# ToolPCB.net
KiCad netlist of a schematic drawn in EAGLE
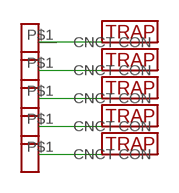
[diagram p0: schematic, sheet 1]

(export (version "E")
  (design (tool "Eeschema 10.0.6"))
  (components
    (comp (ref "U$1")
      (value "MOLEX-LITE-TRAP")
      (footprint "eagle-import:MOLEX-LITE-TRAP")
      (libsource (lib "eagle-import") (part "MOLEX-LITE-TRAP"))
    )
    (comp (ref "U$2")
      (value "MOLEX-LITE-TRAP")
      (footprint "eagle-import:MOLEX-LITE-TRAP")
      (libsource (lib "eagle-import") (part "MOLEX-LITE-TRAP"))
    )
    (comp (ref "U$3")
      (value "MOLEX-LITE-TRAP")
      (footprint "eagle-import:MOLEX-LITE-TRAP")
      (libsource (lib "eagle-import") (part "MOLEX-LITE-TRAP"))
    )
    (comp (ref "U$4")
      (value "MOLEX-LITE-TRAP")
      (footprint "eagle-import:MOLEX-LITE-TRAP")
      (libsource (lib "eagle-import") (part "MOLEX-LITE-TRAP"))
    )
    (comp (ref "U$5")
      (value "MOLEX-LITE-TRAP")
      (footprint "eagle-import:MOLEX-LITE-TRAP")
      (libsource (lib "eagle-import") (part "MOLEX-LITE-TRAP"))
    )
    (comp (ref "U$6")
      (value "B_CONTACT")
      (footprint "eagle-import:B_CONTACT")
      (libsource (lib "eagle-import") (part "B_CONTACT"))
    )
    (comp (ref "U$7")
      (value "B_CONTACT")
      (footprint "eagle-import:B_CONTACT")
      (libsource (lib "eagle-import") (part "B_CONTACT"))
    )
    (comp (ref "U$8")
      (value "B_CONTACT")
      (footprint "eagle-import:B_CONTACT")
      (libsource (lib "eagle-import") (part "B_CONTACT"))
    )
    (comp (ref "U$9")
      (value "B_CONTACT")
      (footprint "eagle-import:B_CONTACT")
      (libsource (lib "eagle-import") (part "B_CONTACT"))
    )
    (comp (ref "U$10")
      (value "B_CONTACT")
      (footprint "eagle-import:B_CONTACT")
      (libsource (lib "eagle-import") (part "B_CONTACT"))
    )
  )
  (nets
    (net (code "1") (name "Net-(U$1-CON)") (class "Default")
      (node (ref "U$1") (pin "TRAP") (pinfunction "CON_TRAP") (pintype "bidirectional"))
      (node (ref "U$8") (pin "P$1") (pinfunction "CNCT_P$1") (pintype "bidirectional"))
    )
    (net (code "2") (name "Net-(U$2-CON)") (class "Default")
      (node (ref "U$2") (pin "TRAP") (pinfunction "CON_TRAP") (pintype "bidirectional"))
      (node (ref "U$7") (pin "P$1") (pinfunction "CNCT_P$1") (pintype "bidirectional"))
    )
    (net (code "3") (name "Net-(U$3-CON)") (class "Default")
      (node (ref "U$3") (pin "TRAP") (pinfunction "CON_TRAP") (pintype "bidirectional"))
      (node (ref "U$6") (pin "P$1") (pinfunction "CNCT_P$1") (pintype "bidirectional"))
    )
    (net (code "4") (name "Net-(U$4-CON)") (class "Default")
      (node (ref "U$4") (pin "TRAP") (pinfunction "CON_TRAP") (pintype "bidirectional"))
      (node (ref "U$9") (pin "P$1") (pinfunction "CNCT_P$1") (pintype "bidirectional"))
    )
    (net (code "5") (name "Net-(U$10-CNCT)") (class "Default")
      (node (ref "U$10") (pin "P$1") (pinfunction "CNCT_P$1") (pintype "bidirectional"))
      (node (ref "U$5") (pin "TRAP") (pinfunction "CON_TRAP") (pintype "bidirectional"))
    )
  )
)
